# CAN.net
KiCad netlist of a schematic drawn in Altium Designer
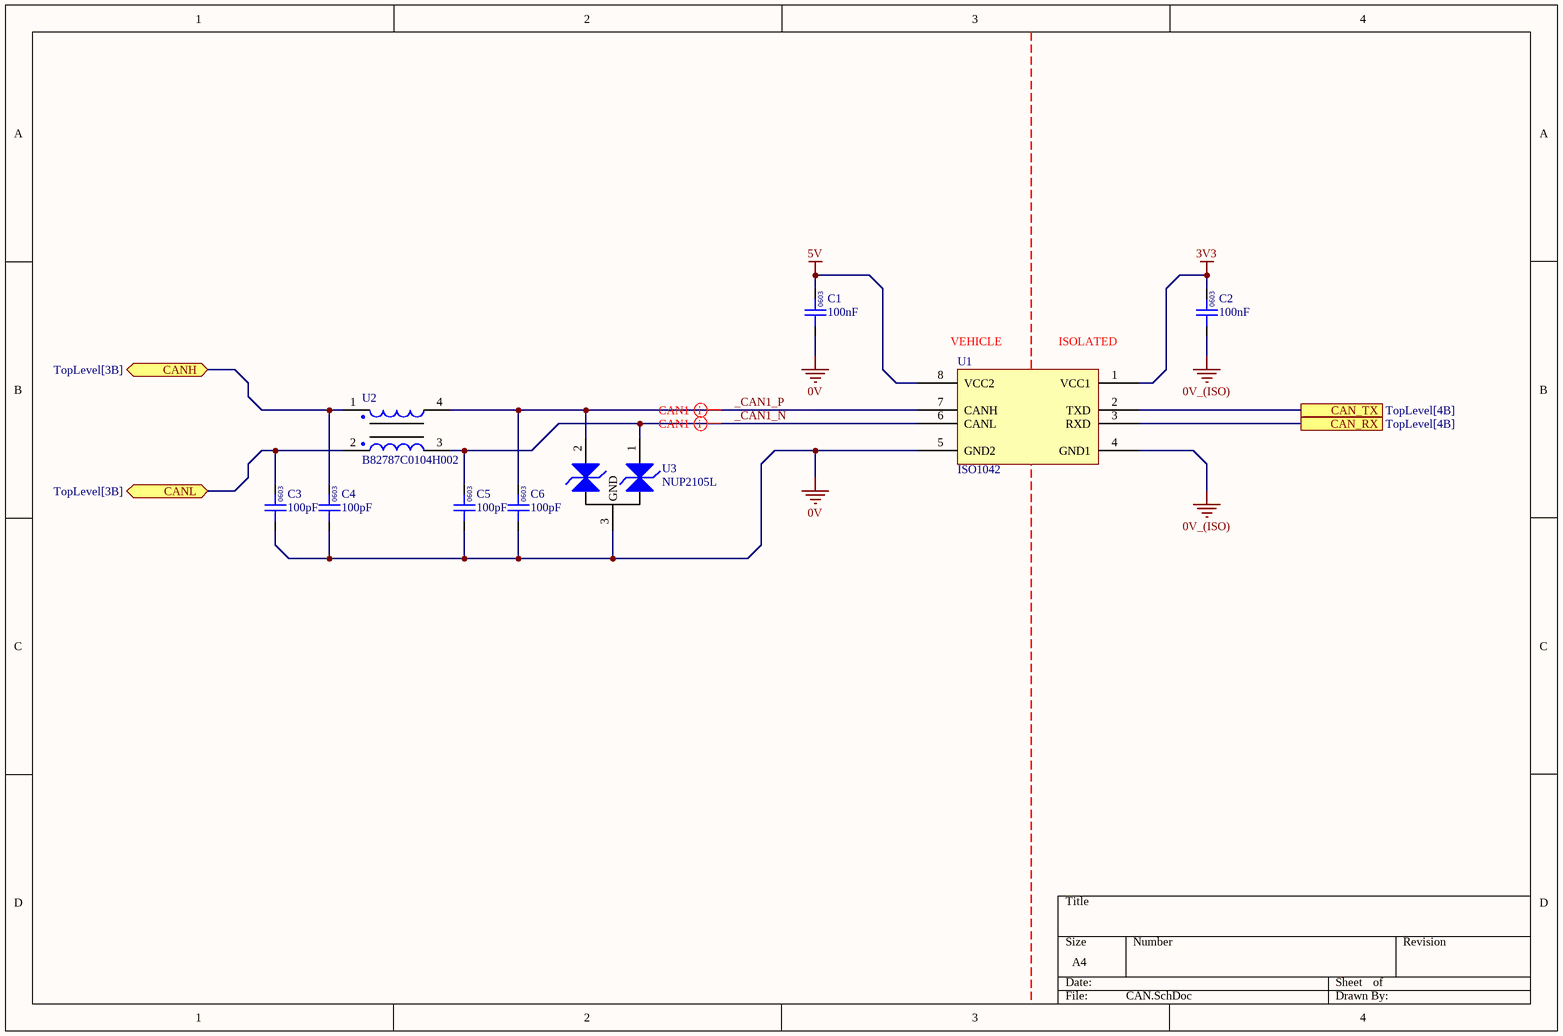
[diagram p0: CAN.SchDoc]

(export (version "E")
  (design (tool "Eeschema 10.0.6"))
  (components
    (comp (ref "C1")
      (value "100nF")
      (footprint "0603")
      (fields
        (field (name "PART NUMBER") "GCM188L81H104KA57D")
        (field (name "MANUFACTURER") "muRata")
        (field (name "TOLERANCE") "±10%")
      )
      (libsource (lib "ts_standard_library") (part "Capacitor 0603"))
    )
    (comp (ref "C2")
      (value "100nF")
      (footprint "0603")
      (fields
        (field (name "PART NUMBER") "GCM188L81H104KA57D")
        (field (name "MANUFACTURER") "muRata")
        (field (name "TOLERANCE") "±10%")
      )
      (libsource (lib "ts_standard_library") (part "Capacitor 0603"))
    )
    (comp (ref "C3")
      (value "100pF")
      (footprint "0603")
      (fields
        (field (name "PART NUMBER") "GRM1885C1H101JA01D")
        (field (name "MANUFACTURER") "Murata Electronics")
        (field (name "TOLERANCE") "±5%")
      )
      (libsource (lib "ts_standard_library") (part "Capacitor 0603"))
    )
    (comp (ref "C4")
      (value "100pF")
      (footprint "0603")
      (fields
        (field (name "PART NUMBER") "GRM1885C1H101JA01D")
        (field (name "MANUFACTURER") "Murata Electronics")
        (field (name "TOLERANCE") "±5%")
      )
      (libsource (lib "ts_standard_library") (part "Capacitor 0603"))
    )
    (comp (ref "C5")
      (value "100pF")
      (footprint "0603")
      (fields
        (field (name "PART NUMBER") "GRM1885C1H101JA01D")
        (field (name "MANUFACTURER") "Murata Electronics")
        (field (name "TOLERANCE") "±5%")
      )
      (libsource (lib "ts_standard_library") (part "Capacitor 0603"))
    )
    (comp (ref "C6")
      (value "100pF")
      (footprint "0603")
      (fields
        (field (name "PART NUMBER") "GRM1885C1H101JA01D")
        (field (name "MANUFACTURER") "Murata Electronics")
        (field (name "TOLERANCE") "±5%")
      )
      (libsource (lib "ts_standard_library") (part "Capacitor 0603"))
    )
    (comp (ref "U1")
      (value "ISO1042")
      (footprint "TI-SOIC-8")
      (description "IC CAN TRANSCEIVER 1/1 8SOIC")
      (fields
        (field (name "MANUFACTURER") "Texas Instruments")
        (field (name "DIGIKEY PART NUMBER") "296-ISO1042BQDWVQ1-ND")
      )
      (libsource (lib "ts_standard_library") (part "ISO1042"))
    )
    (comp (ref "U2")
      (value "B82787C0104H002")
      (footprint "TDK 4-PC Pad")
      (fields
        (field (name "MANUFACTURER") "EPCOS (TDK)")
        (field (name "DIGIKEY PART NUMBER") "495-4598-1-ND")
      )
      (libsource (lib "ts_standard_library") (part "B82787C0104H002"))
    )
    (comp (ref "U3")
      (value "NUP2105L")
      (footprint "ON SOT-23")
      (description "Dual Line CAN Bus Protector")
      (fields
        (field (name "MANUFACTURER") "ON Semiconductor")
        (field (name "DIGIKEY PART NUMBER") "NUP2105LT1GOSCT-ND")
      )
      (libsource (lib "ts_standard_library") (part "NUP2105L"))
    )
  )
  (nets
    (net (code "1") (name "/CANH") (class "Default")
      (node (ref "C4") (pin "2") (pinfunction "2_2") (pintype "passive"))
      (node (ref "U2") (pin "1") (pinfunction "1_1") (pintype "passive"))
    )
    (net (code "2") (name "/CANL") (class "Default")
      (node (ref "C3") (pin "2") (pinfunction "2_2") (pintype "passive"))
      (node (ref "U2") (pin "2") (pinfunction "2_2") (pintype "passive"))
    )
    (net (code "3") (name "/CAN_RX") (class "Default")
      (node (ref "U1") (pin "3") (pinfunction "RXD_3") (pintype "passive"))
    )
    (net (code "4") (name "/CAN_TX") (class "Default")
      (node (ref "U1") (pin "2") (pinfunction "TXD_2") (pintype "passive"))
    )
    (net (code "5") (name "/_CAN1_N") (class "Default")
      (node (ref "C5") (pin "2") (pinfunction "2_2") (pintype "passive"))
      (node (ref "U1") (pin "6") (pinfunction "CANL_6") (pintype "passive"))
      (node (ref "U2") (pin "3") (pinfunction "3_3") (pintype "passive"))
      (node (ref "U3") (pin "1") (pinfunction "CAN_H_1") (pintype "passive"))
    )
    (net (code "6") (name "/_CAN1_P") (class "Default")
      (node (ref "C6") (pin "2") (pinfunction "2_2") (pintype "passive"))
      (node (ref "U1") (pin "7") (pinfunction "CANH_7") (pintype "passive"))
      (node (ref "U2") (pin "4") (pinfunction "4_4") (pintype "passive"))
      (node (ref "U3") (pin "2") (pinfunction "CAN_L_2") (pintype "passive"))
    )
    (net (code "7") (name "0V") (class "Default")
      (node (ref "C1") (pin "1") (pinfunction "1_1") (pintype "passive"))
      (node (ref "C3") (pin "1") (pinfunction "1_1") (pintype "passive"))
      (node (ref "C4") (pin "1") (pinfunction "1_1") (pintype "passive"))
      (node (ref "C5") (pin "1") (pinfunction "1_1") (pintype "passive"))
      (node (ref "C6") (pin "1") (pinfunction "1_1") (pintype "passive"))
      (node (ref "U1") (pin "5") (pinfunction "GND2_5") (pintype "passive"))
      (node (ref "U3") (pin "3") (pinfunction "GND_3") (pintype "passive"))
    )
    (net (code "8") (name "0V_(ISO)") (class "Default")
      (node (ref "C2") (pin "1") (pinfunction "1_1") (pintype "passive"))
      (node (ref "U1") (pin "4") (pinfunction "GND1_4") (pintype "passive"))
    )
    (net (code "9") (name "3V3") (class "Default")
      (node (ref "C2") (pin "2") (pinfunction "2_2") (pintype "passive"))
      (node (ref "U1") (pin "1") (pinfunction "VCC1_1") (pintype "passive"))
    )
    (net (code "10") (name "5V") (class "Default")
      (node (ref "C1") (pin "2") (pinfunction "2_2") (pintype "passive"))
      (node (ref "U1") (pin "8") (pinfunction "VCC2_8") (pintype "passive"))
    )
  )
)
